# SCH_Universal_Endstop_ZAxis_Dumb_2023-11.net
KiCad netlist of a schematic drawn in EasyEDA
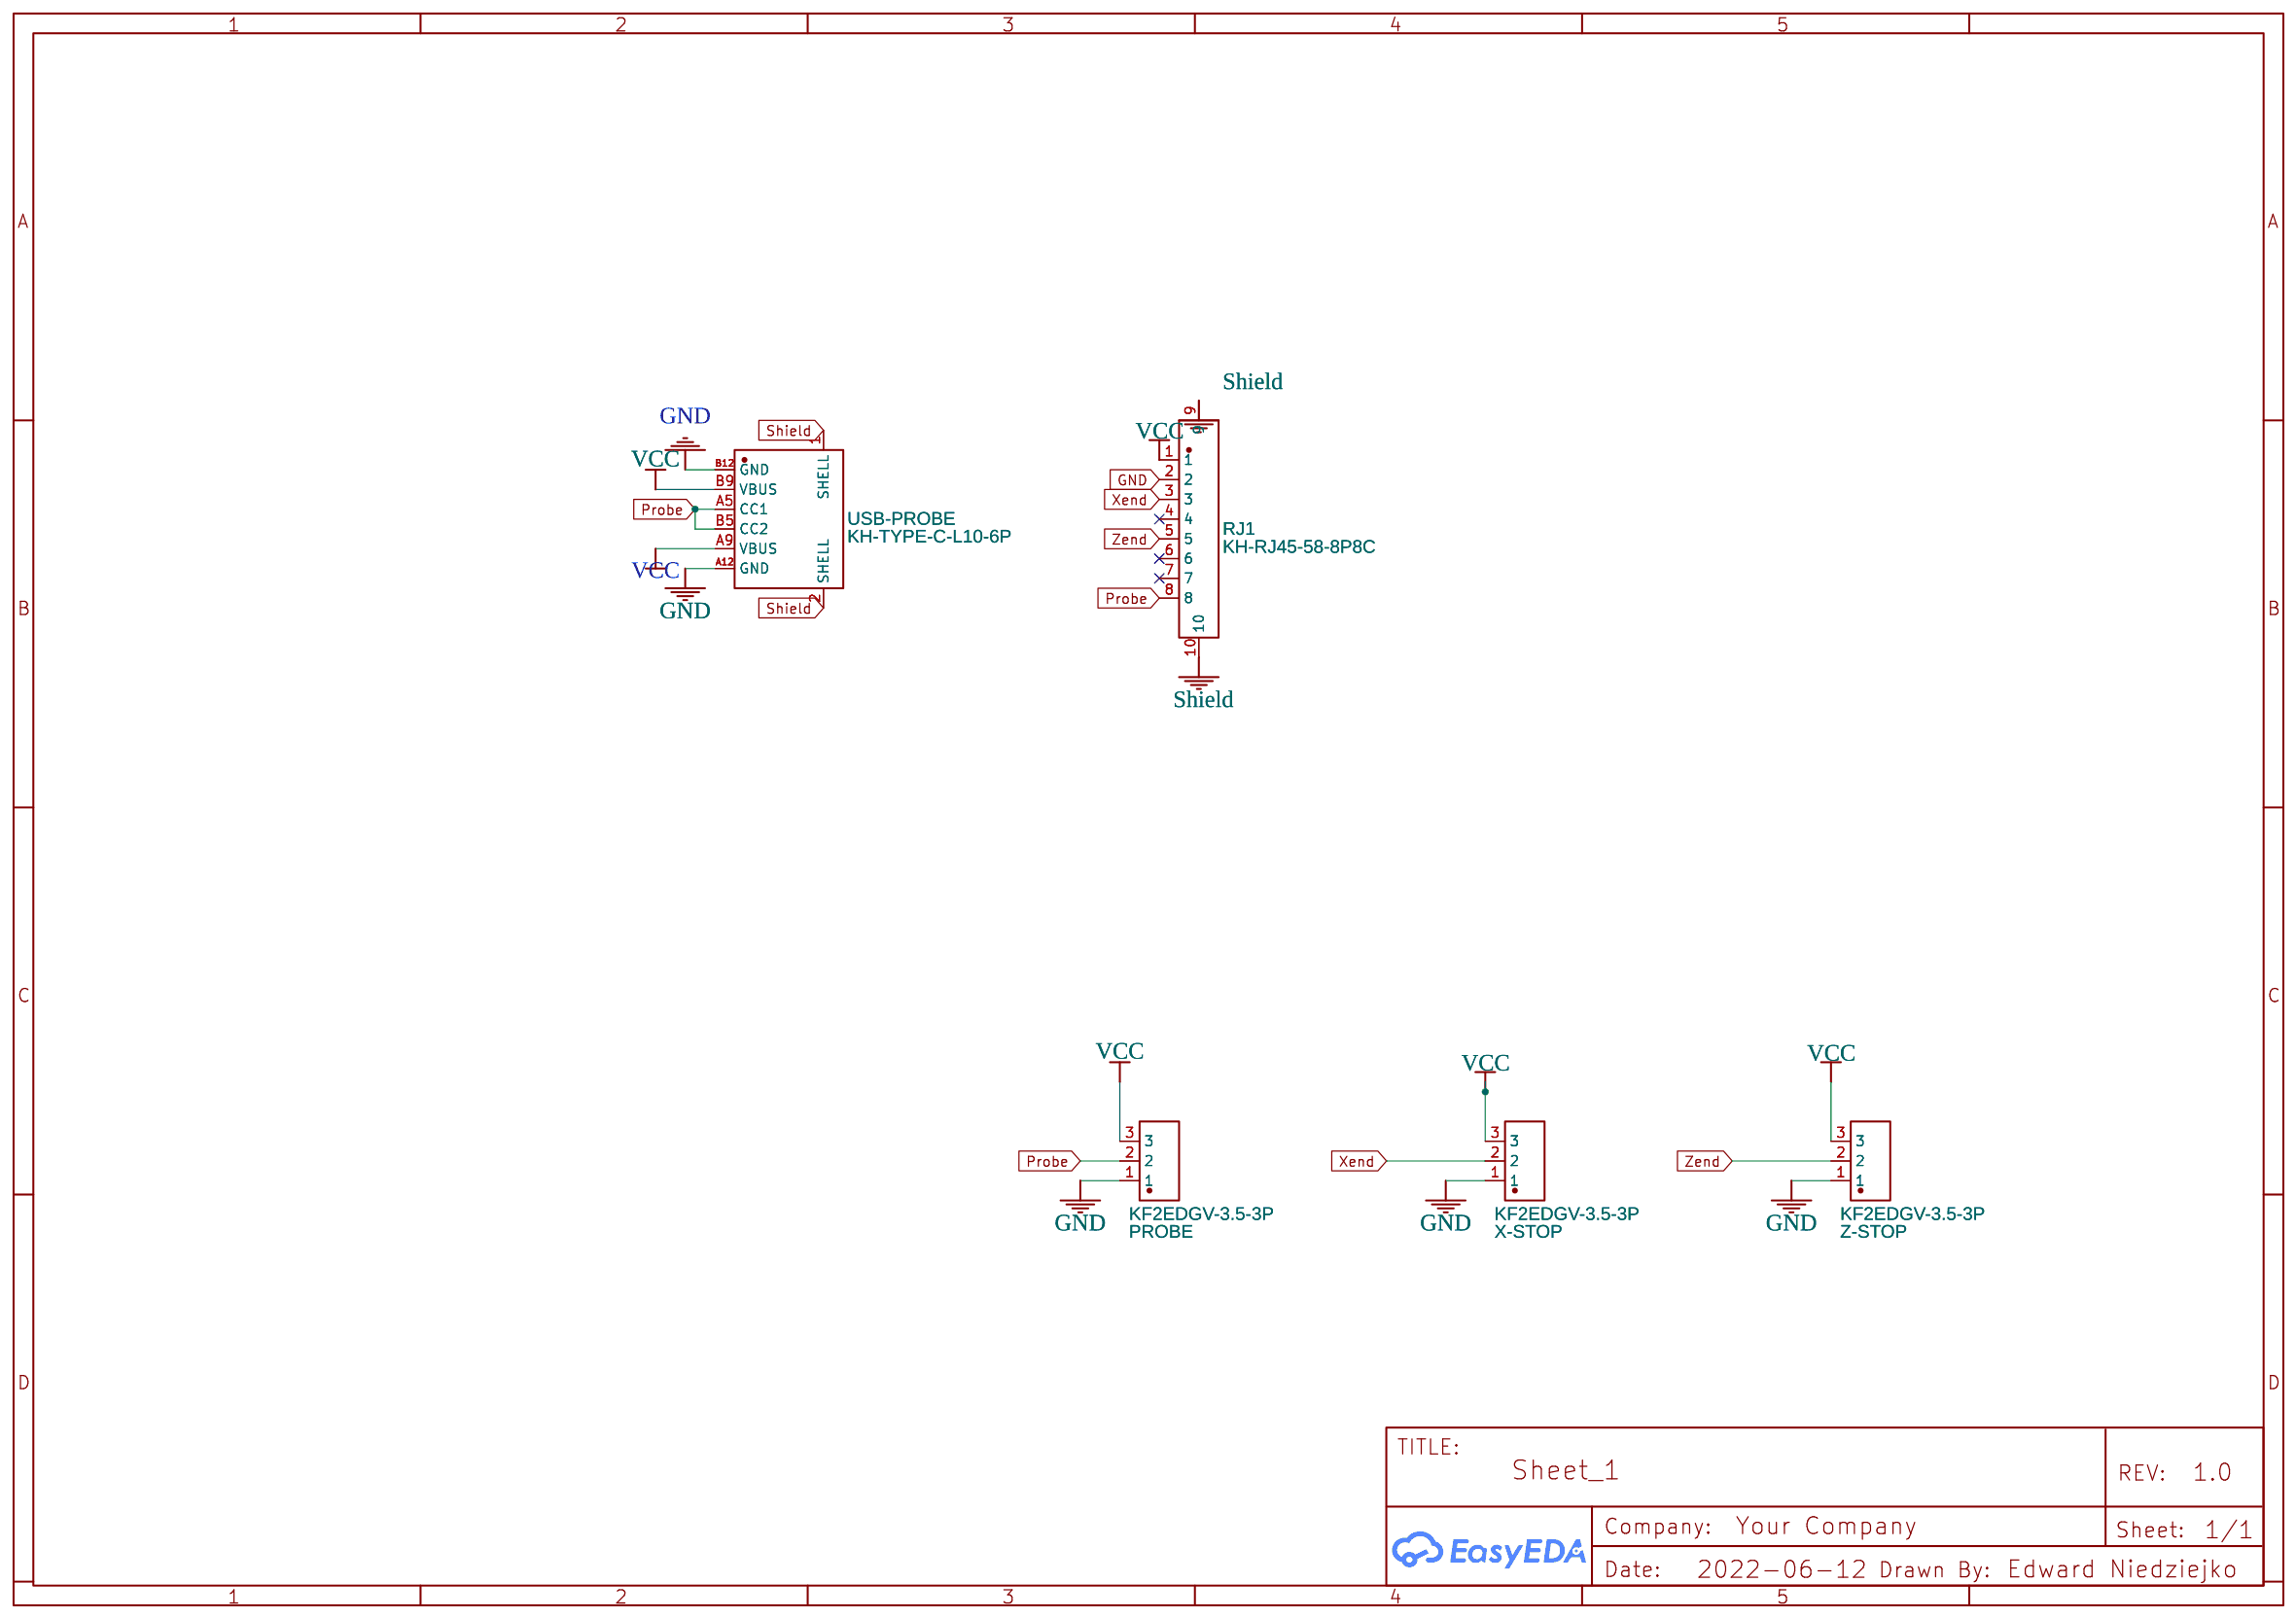
[diagram p0: schematic sheet]

(export (version "E")
  (design (tool "Eeschema 10.0.6"))
  (components
    (comp (ref "PROBE")
      (value "KF2EDGV-3.5-3P")
      (fields (field (name "Manufacturer") "Cixi Kefa Elec"))
      (libsource (lib "") (part "KF2EDGV-3.5-3P_1"))
    )
    (comp (ref "RJ1")
      (value "KH-RJ45-58-8P8C")
      (fields (field (name "Manufacturer") "kinghelm(金航标)"))
      (libsource (lib "") (part "KH-RJ45-58-8P8C"))
    )
    (comp (ref "USB-PROBE")
      (value "KH-TYPE-C-L10-6P")
      (fields (field (name "Manufacturer") "kinghelm(金航标)"))
      (libsource (lib "") (part "KH-TYPE-C-L10-6P"))
    )
    (comp (ref "X-STOP")
      (value "KF2EDGV-3.5-3P")
      (fields (field (name "Manufacturer") "Cixi Kefa Elec"))
      (libsource (lib "") (part "KF2EDGV-3.5-3P_2"))
    )
    (comp (ref "Z-STOP")
      (value "KF2EDGV-3.5-3P")
      (fields (field (name "Manufacturer") "Cixi Kefa Elec"))
      (libsource (lib "") (part "KF2EDGV-3.5-3P"))
    )
  )
  (nets
    (net (code "1") (name "GND") (class "Default")
      (node (ref "PROBE") (pin "1") (pinfunction "1_1") (pintype "unspecified"))
      (node (ref "RJ1") (pin "2") (pinfunction "2_2") (pintype "unspecified"))
      (node (ref "USB-PROBE") (pin "A12") (pinfunction "GND_A12") (pintype "unspecified"))
      (node (ref "USB-PROBE") (pin "B12") (pinfunction "GND_B12") (pintype "unspecified"))
      (node (ref "X-STOP") (pin "1") (pinfunction "1_1") (pintype "unspecified"))
      (node (ref "Z-STOP") (pin "1") (pinfunction "1_1") (pintype "unspecified"))
    )
    (net (code "2") (name "Probe") (class "Default")
      (node (ref "PROBE") (pin "2") (pinfunction "2_2") (pintype "unspecified"))
      (node (ref "RJ1") (pin "8") (pinfunction "8_8") (pintype "unspecified"))
      (node (ref "USB-PROBE") (pin "A5") (pinfunction "CC1_A5") (pintype "unspecified"))
      (node (ref "USB-PROBE") (pin "B5") (pinfunction "CC2_B5") (pintype "unspecified"))
    )
    (net (code "3") (name "Shield") (class "Default")
      (node (ref "RJ1") (pin "10") (pinfunction "10_10") (pintype "unspecified"))
      (node (ref "RJ1") (pin "9") (pinfunction "9_9") (pintype "unspecified"))
      (node (ref "USB-PROBE") (pin "1") (pinfunction "SHELL_1") (pintype "unspecified"))
      (node (ref "USB-PROBE") (pin "2") (pinfunction "SHELL_2") (pintype "unspecified"))
    )
    (net (code "4") (name "VCC") (class "Default")
      (node (ref "PROBE") (pin "3") (pinfunction "3_3") (pintype "unspecified"))
      (node (ref "RJ1") (pin "1") (pinfunction "1_1") (pintype "unspecified"))
      (node (ref "USB-PROBE") (pin "A9") (pinfunction "VBUS_A9") (pintype "unspecified"))
      (node (ref "USB-PROBE") (pin "B9") (pinfunction "VBUS_B9") (pintype "unspecified"))
      (node (ref "X-STOP") (pin "3") (pinfunction "3_3") (pintype "unspecified"))
      (node (ref "Z-STOP") (pin "3") (pinfunction "3_3") (pintype "unspecified"))
    )
    (net (code "5") (name "Xend") (class "Default")
      (node (ref "RJ1") (pin "3") (pinfunction "3_3") (pintype "unspecified"))
      (node (ref "X-STOP") (pin "2") (pinfunction "2_2") (pintype "unspecified"))
    )
    (net (code "6") (name "Zend") (class "Default")
      (node (ref "RJ1") (pin "5") (pinfunction "5_5") (pintype "unspecified"))
      (node (ref "Z-STOP") (pin "2") (pinfunction "2_2") (pintype "unspecified"))
    )
    (net (code "7") (name "unconnected-(RJ1-Pad4)") (class "Default")
      (node (ref "RJ1") (pin "4") (pinfunction "4_4") (pintype "unspecified+no_connect"))
    )
    (net (code "8") (name "unconnected-(RJ1-Pad6)") (class "Default")
      (node (ref "RJ1") (pin "6") (pinfunction "6_6") (pintype "unspecified+no_connect"))
    )
    (net (code "9") (name "unconnected-(RJ1-Pad7)") (class "Default")
      (node (ref "RJ1") (pin "7") (pinfunction "7_7") (pintype "unspecified+no_connect"))
    )
  )
)
